# ftdi_prototype.net
KiCad netlist of a schematic drawn in EAGLE
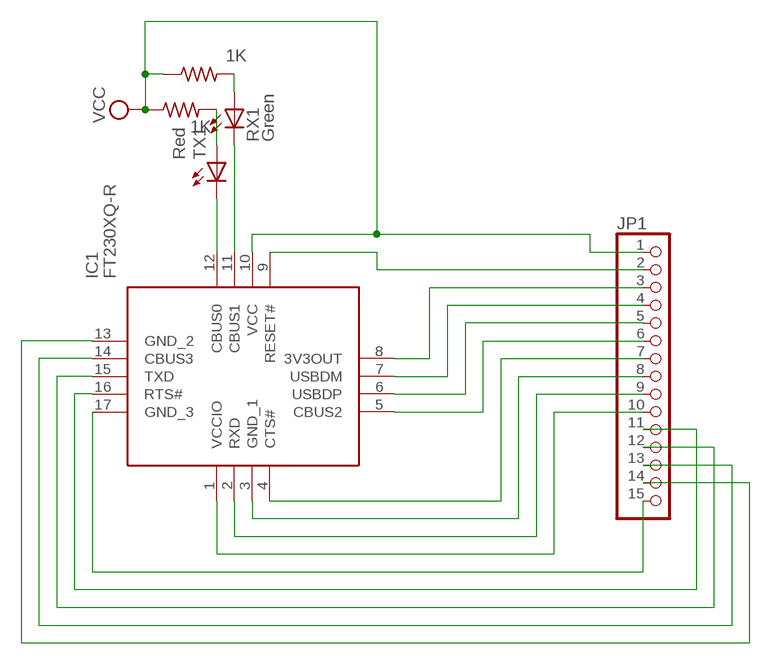
[diagram p0: schematic, sheet 1]

(export (version "E")
  (design (tool "Eeschema 10.0.6"))
  (components
    (comp (ref "IC1")
      (value "FT230XQ-R")
      (footprint "eagle-import:QFN65P400X400X80-17N")
      (fields (field (name "MOUSER_PART_NUMBER") "895-FT230XQ-R"))
      (libsource (lib "eagle-import") (part "FT230XQ-R"))
    )
    (comp (ref "JP1")
      (value "PINHD-1X15")
      (footprint "eagle-import:1X15")
      (libsource (lib "eagle-import") (part "PINHD-1X15"))
    )
    (comp (ref "R4")
      (value "1K")
      (footprint "eagle-import:R0805")
      (libsource (lib "eagle-import") (part "R-US_R0805"))
    )
    (comp (ref "R5")
      (value "1K")
      (footprint "eagle-import:R0805")
      (libsource (lib "eagle-import") (part "R-US_R0805"))
    )
    (comp (ref "RX1")
      (value "Green")
      (footprint "eagle-import:CHIP-LED0805")
      (libsource (lib "eagle-import") (part "LEDCHIP-LED0805"))
    )
    (comp (ref "TX1")
      (value "Red")
      (footprint "eagle-import:CHIP-LED0805")
      (libsource (lib "eagle-import") (part "LEDCHIP-LED0805"))
    )
  )
  (nets
    (net (code "1") (name "Net-(IC1-3V3OUT)") (class "Default")
      (node (ref "IC1") (pin "8") (pinfunction "3V3OUT_8") (pintype "bidirectional"))
      (node (ref "JP1") (pin "3") (pinfunction "3_3") (pintype "passive"))
    )
    (net (code "2") (name "Net-(IC1-CBUS0)") (class "Default")
      (node (ref "IC1") (pin "12") (pinfunction "CBUS0_12") (pintype "bidirectional"))
      (node (ref "TX1") (pin "C") (pinfunction "C_C") (pintype "passive"))
    )
    (net (code "3") (name "Net-(IC1-CBUS1)") (class "Default")
      (node (ref "IC1") (pin "11") (pinfunction "CBUS1_11") (pintype "bidirectional"))
      (node (ref "RX1") (pin "C") (pinfunction "C_C") (pintype "passive"))
    )
    (net (code "4") (name "Net-(IC1-CBUS2)") (class "Default")
      (node (ref "IC1") (pin "5") (pinfunction "CBUS2_5") (pintype "bidirectional"))
      (node (ref "JP1") (pin "6") (pinfunction "6_6") (pintype "passive"))
    )
    (net (code "5") (name "Net-(IC1-CBUS3)") (class "Default")
      (node (ref "IC1") (pin "14") (pinfunction "CBUS3_14") (pintype "bidirectional"))
      (node (ref "JP1") (pin "13") (pinfunction "13_13") (pintype "passive"))
    )
    (net (code "6") (name "Net-(IC1-CTS#)") (class "Default")
      (node (ref "IC1") (pin "4") (pinfunction "CTS#_4") (pintype "bidirectional"))
      (node (ref "JP1") (pin "7") (pinfunction "7_7") (pintype "passive"))
    )
    (net (code "7") (name "Net-(IC1-GND_1)") (class "Default")
      (node (ref "IC1") (pin "3") (pinfunction "GND_1_3") (pintype "bidirectional"))
      (node (ref "JP1") (pin "8") (pinfunction "8_8") (pintype "passive"))
    )
    (net (code "8") (name "Net-(IC1-GND_2)") (class "Default")
      (node (ref "IC1") (pin "13") (pinfunction "GND_2_13") (pintype "bidirectional"))
      (node (ref "JP1") (pin "14") (pinfunction "14_14") (pintype "passive"))
    )
    (net (code "9") (name "Net-(IC1-GND_3)") (class "Default")
      (node (ref "IC1") (pin "17") (pinfunction "GND_3_17") (pintype "bidirectional"))
      (node (ref "JP1") (pin "15") (pinfunction "15_15") (pintype "passive"))
    )
    (net (code "10") (name "Net-(IC1-RESET#)") (class "Default")
      (node (ref "IC1") (pin "9") (pinfunction "RESET#_9") (pintype "bidirectional"))
      (node (ref "JP1") (pin "2") (pinfunction "2_2") (pintype "passive"))
    )
    (net (code "11") (name "Net-(IC1-RTS#)") (class "Default")
      (node (ref "IC1") (pin "16") (pinfunction "RTS#_16") (pintype "bidirectional"))
      (node (ref "JP1") (pin "11") (pinfunction "11_11") (pintype "passive"))
    )
    (net (code "12") (name "Net-(IC1-RXD)") (class "Default")
      (node (ref "IC1") (pin "2") (pinfunction "RXD_2") (pintype "bidirectional"))
      (node (ref "JP1") (pin "9") (pinfunction "9_9") (pintype "passive"))
    )
    (net (code "13") (name "Net-(IC1-TXD)") (class "Default")
      (node (ref "IC1") (pin "15") (pinfunction "TXD_15") (pintype "bidirectional"))
      (node (ref "JP1") (pin "12") (pinfunction "12_12") (pintype "passive"))
    )
    (net (code "14") (name "Net-(IC1-USBDM)") (class "Default")
      (node (ref "IC1") (pin "7") (pinfunction "USBDM_7") (pintype "bidirectional"))
      (node (ref "JP1") (pin "4") (pinfunction "4_4") (pintype "passive"))
    )
    (net (code "15") (name "Net-(IC1-USBDP)") (class "Default")
      (node (ref "IC1") (pin "6") (pinfunction "USBDP_6") (pintype "bidirectional"))
      (node (ref "JP1") (pin "5") (pinfunction "5_5") (pintype "passive"))
    )
    (net (code "16") (name "Net-(IC1-VCCIO)") (class "Default")
      (node (ref "IC1") (pin "1") (pinfunction "VCCIO_1") (pintype "bidirectional"))
      (node (ref "JP1") (pin "10") (pinfunction "10_10") (pintype "passive"))
    )
    (net (code "17") (name "Net-(R4-Pad2)") (class "Default")
      (node (ref "R4") (pin "2") (pinfunction "2_2") (pintype "passive"))
      (node (ref "RX1") (pin "A") (pinfunction "A_A") (pintype "passive"))
    )
    (net (code "18") (name "Net-(R5-Pad2)") (class "Default")
      (node (ref "R5") (pin "2") (pinfunction "2_2") (pintype "passive"))
      (node (ref "TX1") (pin "A") (pinfunction "A_A") (pintype "passive"))
    )
    (net (code "19") (name "VCC") (class "Default")
      (node (ref "IC1") (pin "10") (pinfunction "VCC_10") (pintype "bidirectional"))
      (node (ref "JP1") (pin "1") (pinfunction "1_1") (pintype "passive"))
      (node (ref "R4") (pin "1") (pinfunction "1_1") (pintype "passive"))
      (node (ref "R5") (pin "1") (pinfunction "1_1") (pintype "passive"))
    )
  )
)
